# dwm1000arduino.net
KiCad netlist of a schematic drawn in Altium Designer
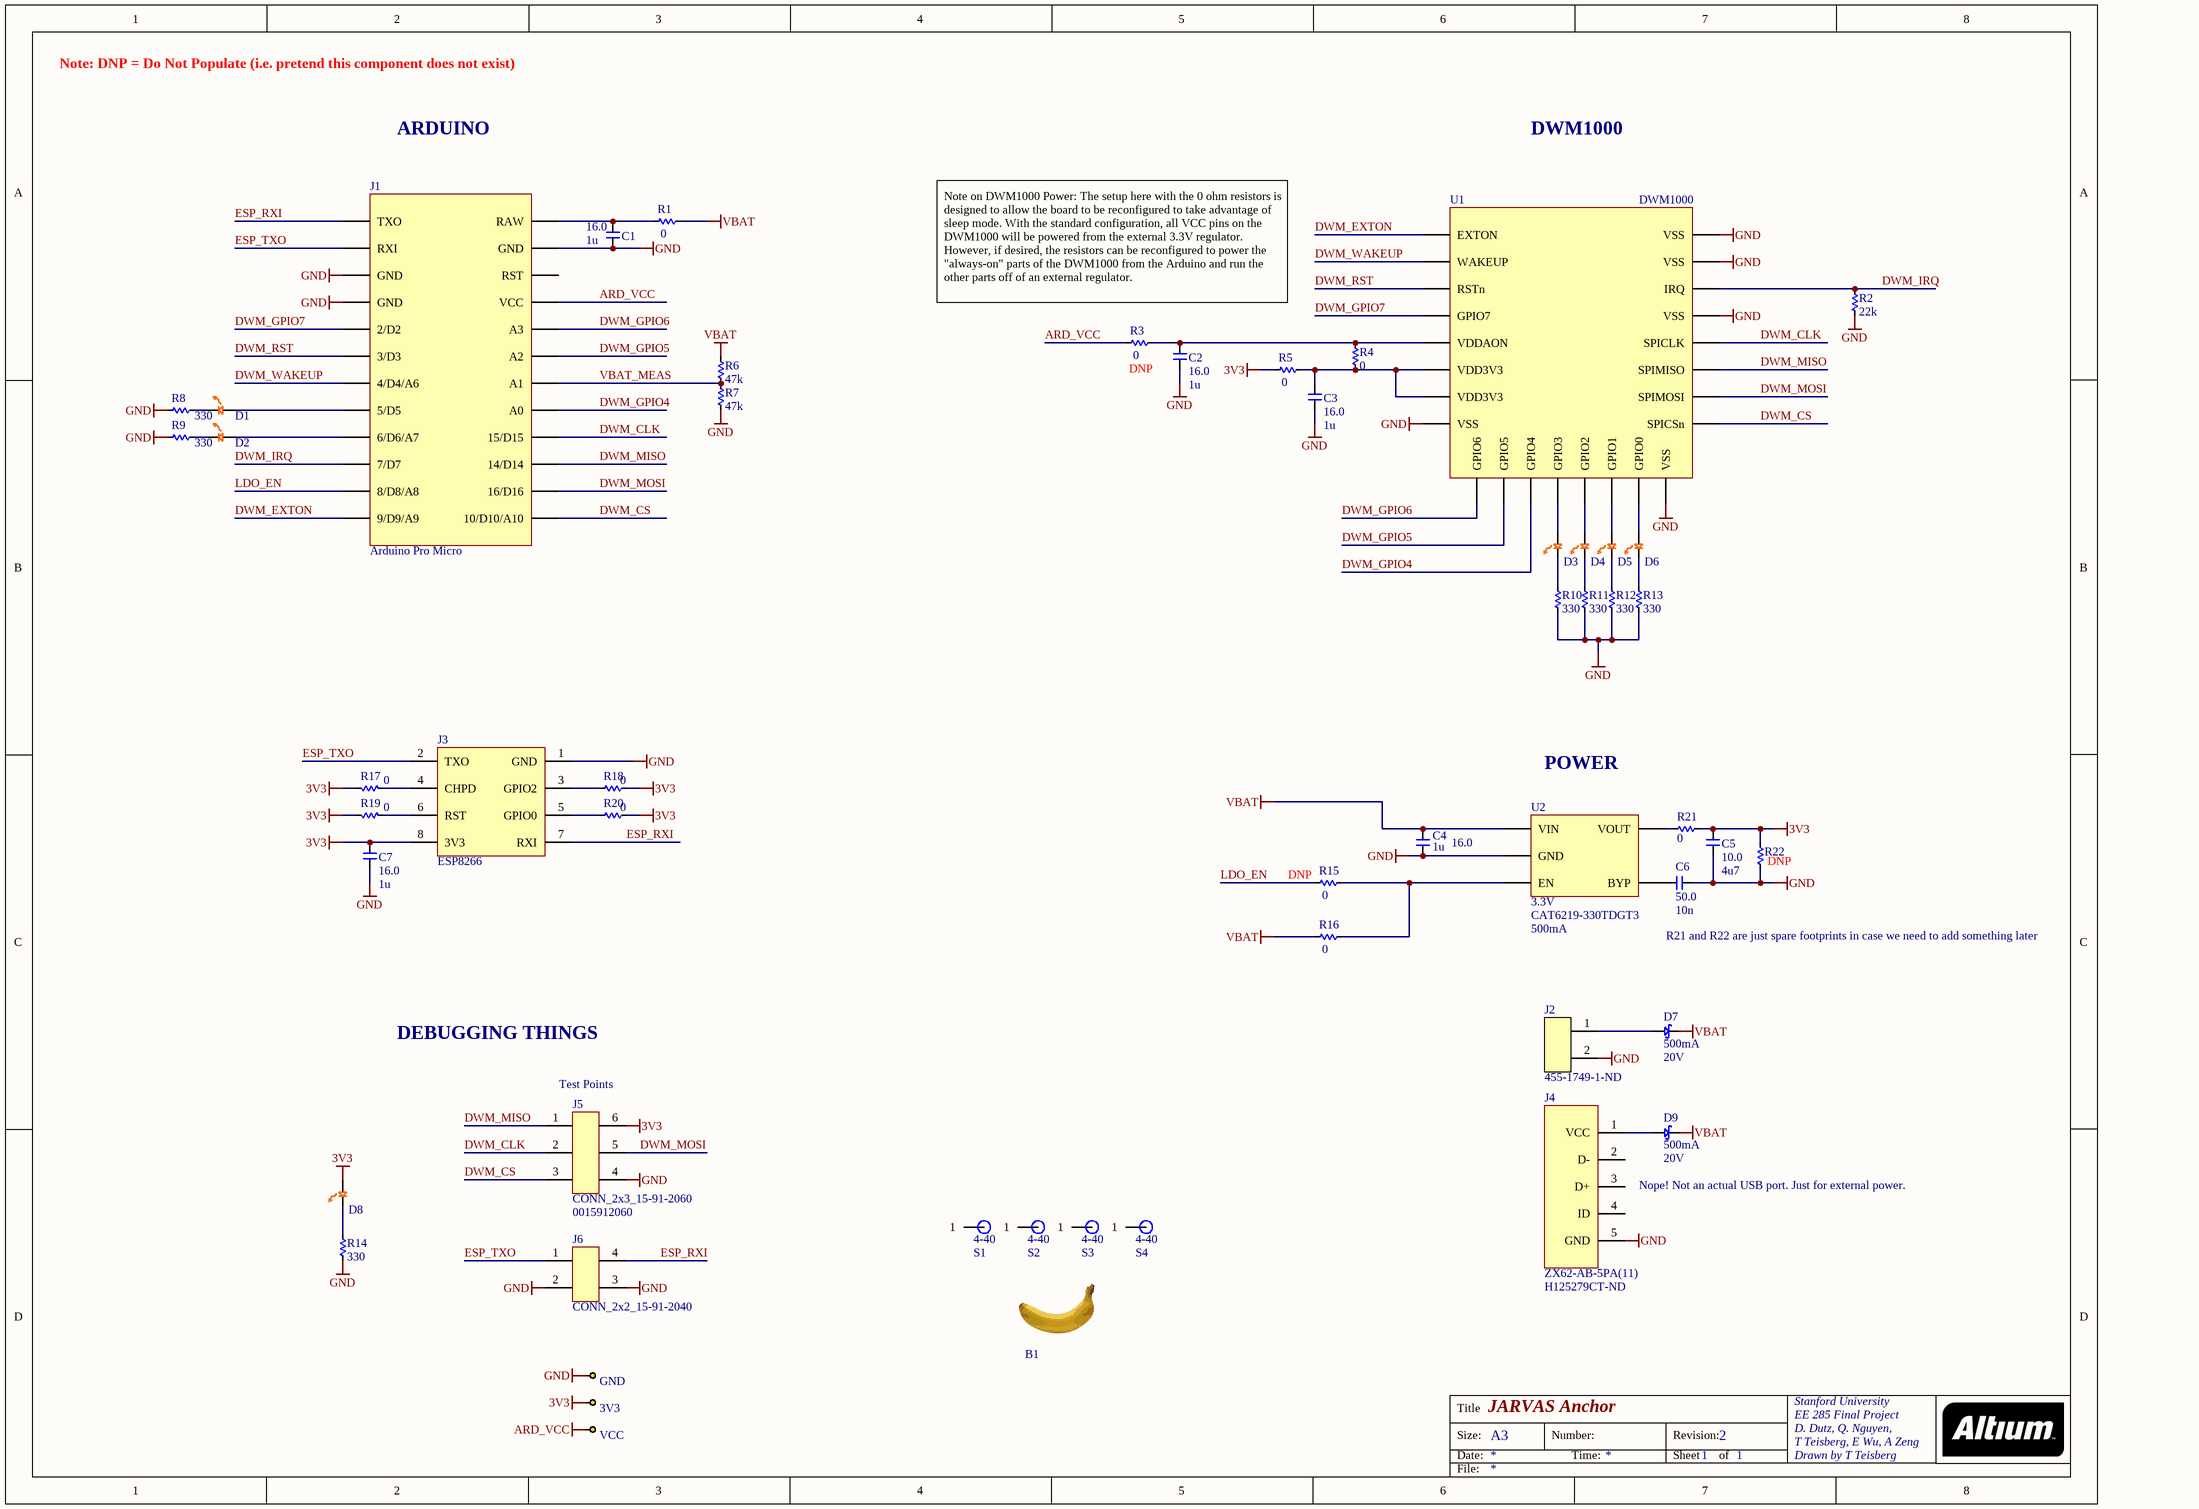
[diagram p0: dwm1000arduino.SchDoc]

(export (version "E")
  (design (tool "Eeschema 10.0.6"))
  (components
    (comp (ref "3V3")
      (value "TEST_KEYSTONE5015")
      (footprint "TP_KEYSTONE_5015")
      (description "PC TEST POINT MINIATURE SMT")
      (fields
        (field (name "MANUFACTURER") "Keystone Electronics")
        (field (name "MANUFACTURER PART NUMBER") "5015")
      )
      (libsource (lib "SSI") (part "TEST_KEYSTONE5015"))
    )
    (comp (ref "B1")
      (value "Banananannaa!")
      (footprint "BANANA_OPEN")
      (description "Banana for scale")
      (libsource (lib "SSI") (part "BANANA"))
    )
    (comp (ref "C1")
      (value "__template_cap")
      (footprint "C0603")
      (fields
        (field (name "VOLTAGE") "16.0")
        (field (name "HUMAN_VALUE") "1u")
        (field (name "TOLERANCE") "10%")
      )
      (libsource (lib "sscp") (part "__template_cap"))
    )
    (comp (ref "C2")
      (value "__template_cap")
      (footprint "C0603")
      (fields
        (field (name "VOLTAGE") "16.0")
        (field (name "HUMAN_VALUE") "1u")
        (field (name "TOLERANCE") "10%")
      )
      (libsource (lib "sscp") (part "__template_cap"))
    )
    (comp (ref "C3")
      (value "__template_cap")
      (footprint "C0603")
      (fields
        (field (name "VOLTAGE") "16.0")
        (field (name "HUMAN_VALUE") "1u")
        (field (name "TOLERANCE") "10%")
      )
      (libsource (lib "sscp") (part "__template_cap"))
    )
    (comp (ref "C4")
      (value "__template_cap")
      (footprint "C0603")
      (fields
        (field (name "VOLTAGE") "16.0")
        (field (name "HUMAN_VALUE") "1u")
        (field (name "TOLERANCE") "10%")
      )
      (libsource (lib "sscp") (part "__template_cap"))
    )
    (comp (ref "C5")
      (value "__template_cap")
      (footprint "C0603")
      (fields
        (field (name "VOLTAGE") "10.0")
        (field (name "HUMAN_VALUE") "4u7")
        (field (name "TOLERANCE") "10%")
      )
      (libsource (lib "sscp") (part "__template_cap"))
    )
    (comp (ref "C6")
      (value "__template_cap")
      (footprint "C0603")
      (fields
        (field (name "VOLTAGE") "50.0")
        (field (name "HUMAN_VALUE") "10n")
        (field (name "TOLERANCE") "5%")
      )
      (libsource (lib "sscp") (part "__template_cap"))
    )
    (comp (ref "C7")
      (value "__template_cap")
      (footprint "C0603")
      (fields
        (field (name "VOLTAGE") "16.0")
        (field (name "HUMAN_VALUE") "1u")
        (field (name "TOLERANCE") "10%")
      )
      (libsource (lib "sscp") (part "__template_cap"))
    )
    (comp (ref "D1")
      (value "LED")
      (footprint "LED0603")
      (description "Orange 605nm LED Indication - Discrete 2V 0603 (1608 Metric)")
      (fields
        (field (name "MANUFACTURER") "Lite-On Inc.")
        (field (name "MANUFACTURER PART NUMBER") "LTST-C190KFKT")
      )
      (libsource (lib "ee285") (part "LED_LTST-C190KFKT_ORANGE"))
    )
    (comp (ref "D2")
      (value "LED")
      (footprint "LED0603")
      (description "Orange 605nm LED Indication - Discrete 2V 0603 (1608 Metric)")
      (fields
        (field (name "MANUFACTURER") "Lite-On Inc.")
        (field (name "MANUFACTURER PART NUMBER") "LTST-C190KFKT")
      )
      (libsource (lib "ee285") (part "LED_LTST-C190KFKT_ORANGE"))
    )
    (comp (ref "D3")
      (value "LED")
      (footprint "LED0603")
      (description "Orange 605nm LED Indication - Discrete 2V 0603 (1608 Metric)")
      (fields
        (field (name "MANUFACTURER") "Lite-On Inc.")
        (field (name "MANUFACTURER PART NUMBER") "LTST-C190KFKT")
      )
      (libsource (lib "ee285") (part "LED_LTST-C190KFKT_ORANGE"))
    )
    (comp (ref "D4")
      (value "LED")
      (footprint "LED0603")
      (description "Orange 605nm LED Indication - Discrete 2V 0603 (1608 Metric)")
      (fields
        (field (name "MANUFACTURER") "Lite-On Inc.")
        (field (name "MANUFACTURER PART NUMBER") "LTST-C190KFKT")
      )
      (libsource (lib "ee285") (part "LED_LTST-C190KFKT_ORANGE"))
    )
    (comp (ref "D5")
      (value "LED")
      (footprint "LED0603")
      (description "Orange 605nm LED Indication - Discrete 2V 0603 (1608 Metric)")
      (fields
        (field (name "MANUFACTURER") "Lite-On Inc.")
        (field (name "MANUFACTURER PART NUMBER") "LTST-C190KFKT")
      )
      (libsource (lib "ee285") (part "LED_LTST-C190KFKT_ORANGE"))
    )
    (comp (ref "D6")
      (value "LED")
      (footprint "LED0603")
      (description "Orange 605nm LED Indication - Discrete 2V 0603 (1608 Metric)")
      (fields
        (field (name "MANUFACTURER") "Lite-On Inc.")
        (field (name "MANUFACTURER PART NUMBER") "LTST-C190KFKT")
      )
      (libsource (lib "ee285") (part "LED_LTST-C190KFKT_ORANGE"))
    )
    (comp (ref "D7")
      (value "SCHOTTKY_MBR0520L")
      (footprint "SOD123")
      (description "DIODE SCHOTTKY 0.5A 20V SOD-123")
      (fields
        (field (name "MANUFACTURER") "Fairchild Semiconductor")
        (field (name "MANUFACTURER PART NUMBER") "MBR0520L")
        (field (name "CURRENT - AVERAGE RECTIFIED (IO)") "500mA")
        (field (name "VOLTAGE - DC REVERSE (VR) (MAX)") "20V")
      )
      (libsource (lib "SSI") (part "SCHOTTKY_MBR0520L"))
    )
    (comp (ref "D8")
      (value "LED")
      (footprint "LED0603")
      (description "Orange 605nm LED Indication - Discrete 2V 0603 (1608 Metric)")
      (fields
        (field (name "MANUFACTURER") "Lite-On Inc.")
        (field (name "MANUFACTURER PART NUMBER") "LTST-C190KFKT")
      )
      (libsource (lib "ee285") (part "LED_LTST-C190KFKT_ORANGE"))
    )
    (comp (ref "D9")
      (value "SCHOTTKY_MBR0520L")
      (footprint "SOD123")
      (description "DIODE SCHOTTKY 0.5A 20V SOD-123")
      (fields
        (field (name "MANUFACTURER") "Fairchild Semiconductor")
        (field (name "MANUFACTURER PART NUMBER") "MBR0520L")
        (field (name "CURRENT - AVERAGE RECTIFIED (IO)") "500mA")
        (field (name "VOLTAGE - DC REVERSE (VR) (MAX)") "20V")
      )
      (libsource (lib "SSI") (part "SCHOTTKY_MBR0520L"))
    )
    (comp (ref "GND")
      (value "TEST_KEYSTONE5015")
      (footprint "TP_KEYSTONE_5015")
      (description "PC TEST POINT MINIATURE SMT")
      (fields
        (field (name "MANUFACTURER") "Keystone Electronics")
        (field (name "MANUFACTURER PART NUMBER") "5015")
      )
      (libsource (lib "SSI") (part "TEST_KEYSTONE5015"))
    )
    (comp (ref "J1")
      (value "Arduino Pro Micro")
      (footprint "ArduinoProMicro")
      (description "SFE Arduino Pro Micro 3.3 V / 8 MHz")
      (libsource (lib "ee285") (part "ArduinoProMicro_3V3_8MHz"))
    )
    (comp (ref "J2")
      (value "CONN JST 2POS SMD")
      (footprint "CONN_JST_PH_SM4_2PIN_RA")
      (description "CONN HEADER PH SIDE 2POS 2MM SMD")
      (fields
        (field (name "MANUFACTURER") "JST Sales America Inc.")
        (field (name "MANUFACTURER PART NUMBER") "S2B-PH-SM4-TB(LF)(SN)")
        (field (name "SUPPLIER PART NUMBER 1") "455-1749-1-ND")
      )
      (libsource (lib "SSI") (part "CONN_JST_2_PH"))
    )
    (comp (ref "J3")
      (value "ESP8266")
      (footprint "PCBComponent_1")
      (description "RF TXRX MODULE WIFI TRACE ANT")
      (fields
        (field (name "MANUFACTURER") "SparkFun Electronics")
        (field (name "MANUFACTURER PART NUMBER") "WRL-13678")
      )
      (libsource (lib "ee285") (part "ESP8266_Module"))
    )
    (comp (ref "J4")
      (value "CONN_USB_MICROAB_SMD_R/A")
      (footprint "HIROSE_ZX62-AB-5PA")
      (description "CONN RCPT MICRO USB AB SMD R/A")
      (fields
        (field (name "MANUFACTURER") "Hirose Electric Co Ltd")
        (field (name "MANUFACTURER PART NUMBER") "ZX62-AB-5PA(11)")
        (field (name "SUPPLIER PART NUMBER 1") "H125279CT-ND")
      )
      (libsource (lib "SSI") (part "CONN_USB_MICROAB_SMD_R/A"))
    )
    (comp (ref "J5")
      (value "CONN_2x3_15-91-2060")
      (footprint "MOLEX_15-91-2060")
      (description "CONN HEADER 6POS .100\" VERT TIN")
      (fields
        (field (name "MANUFACTURER") "Molex Inc")
        (field (name "MANUFACTURER PART NUMBER") "0015912060")
      )
      (libsource (lib "SSI") (part "CONN_2x3_15-91-2060"))
    )
    (comp (ref "J6")
      (value "CONN_2x2_15-91-2040")
      (footprint "MOLEX_15-91-2040")
      (description "CONN HEADER 4POS .100\" VERT TIN")
      (libsource (lib "SSI") (part "CONN_2x2_15-91-2040"))
    )
    (comp (ref "R1")
      (value "__template_resistor")
      (footprint "R0603")
      (description "RES SMD 0.0 OHM")
      (fields
        (field (name "MANUFACTURER PART NUMBER") "CRCW06030000Z0EA")
        (field (name "RESISTANCE (MACHINE READABLE)") "0")
        (field (name "MANUFACTURER") "Vishay Dale")
      )
      (libsource (lib "resistor") (part "__template_resistor"))
    )
    (comp (ref "R2")
      (value "22k")
      (footprint "R0603")
      (description "RES SMD 22K OHM 1% 1/10W 0603")
      (fields
        (field (name "MANUFACTURER PART NUMBER") "CRCW060322K0FKEA")
        (field (name "MANUFACTURER") "Vishay Dale")
      )
      (libsource (lib "resistor") (part "__template_resistor"))
    )
    (comp (ref "R3")
      (value "__template_resistor")
      (footprint "R0603")
      (description "RES SMD 0.0 OHM")
      (fields
        (field (name "MANUFACTURER PART NUMBER") "CRCW06030000Z0EA")
        (field (name "RESISTANCE (MACHINE READABLE)") "0")
        (field (name "MANUFACTURER") "Vishay Dale")
        (field (name "DNP") "DNP")
      )
      (libsource (lib "resistor") (part "__template_resistor"))
    )
    (comp (ref "R4")
      (value "__template_resistor")
      (footprint "R0603")
      (description "RES SMD 0.0 OHM")
      (fields
        (field (name "MANUFACTURER PART NUMBER") "CRCW06030000Z0EA")
        (field (name "RESISTANCE (MACHINE READABLE)") "0")
        (field (name "MANUFACTURER") "Vishay Dale")
      )
      (libsource (lib "resistor") (part "__template_resistor"))
    )
    (comp (ref "R5")
      (value "__template_resistor")
      (footprint "R0603")
      (description "RES SMD 0.0 OHM")
      (fields
        (field (name "MANUFACTURER PART NUMBER") "CRCW06030000Z0EA")
        (field (name "RESISTANCE (MACHINE READABLE)") "0")
        (field (name "MANUFACTURER") "Vishay Dale")
      )
      (libsource (lib "resistor") (part "__template_resistor"))
    )
    (comp (ref "R6")
      (value "47k")
      (footprint "R0603")
      (description "RES SMD 47K OHM 1% 1/10W 0603")
      (fields
        (field (name "MANUFACTURER PART NUMBER") "CRCW060347K0FKEA")
        (field (name "MANUFACTURER") "Vishay Dale")
      )
      (libsource (lib "resistor") (part "__template_resistor"))
    )
    (comp (ref "R7")
      (value "47k")
      (footprint "R0603")
      (description "RES SMD 47K OHM 1% 1/10W 0603")
      (fields
        (field (name "MANUFACTURER PART NUMBER") "CRCW060347K0FKEA")
        (field (name "MANUFACTURER") "Vishay Dale")
      )
      (libsource (lib "resistor") (part "__template_resistor"))
    )
    (comp (ref "R8")
      (value "330")
      (footprint "R0603")
      (description "RES SMD 330 OHM 1% 1/10W 0603")
      (fields
        (field (name "MANUFACTURER PART NUMBER") "CRCW0603330RFKEA")
        (field (name "MANUFACTURER") "Vishay Dale")
      )
      (libsource (lib "resistor") (part "__template_resistor"))
    )
    (comp (ref "R9")
      (value "330")
      (footprint "R0603")
      (description "RES SMD 330 OHM 1% 1/10W 0603")
      (fields
        (field (name "MANUFACTURER PART NUMBER") "CRCW0603330RFKEA")
        (field (name "MANUFACTURER") "Vishay Dale")
      )
      (libsource (lib "resistor") (part "__template_resistor"))
    )
    (comp (ref "R10")
      (value "330")
      (footprint "R0603")
      (description "RES SMD 330 OHM 1% 1/10W 0603")
      (fields
        (field (name "MANUFACTURER PART NUMBER") "CRCW0603330RFKEA")
        (field (name "MANUFACTURER") "Vishay Dale")
      )
      (libsource (lib "resistor") (part "__template_resistor"))
    )
    (comp (ref "R11")
      (value "330")
      (footprint "R0603")
      (description "RES SMD 330 OHM 1% 1/10W 0603")
      (fields
        (field (name "MANUFACTURER PART NUMBER") "CRCW0603330RFKEA")
        (field (name "MANUFACTURER") "Vishay Dale")
      )
      (libsource (lib "resistor") (part "__template_resistor"))
    )
    (comp (ref "R12")
      (value "330")
      (footprint "R0603")
      (description "RES SMD 330 OHM 1% 1/10W 0603")
      (fields
        (field (name "MANUFACTURER PART NUMBER") "CRCW0603330RFKEA")
        (field (name "MANUFACTURER") "Vishay Dale")
      )
      (libsource (lib "resistor") (part "__template_resistor"))
    )
    (comp (ref "R13")
      (value "330")
      (footprint "R0603")
      (description "RES SMD 330 OHM 1% 1/10W 0603")
      (fields
        (field (name "MANUFACTURER PART NUMBER") "CRCW0603330RFKEA")
        (field (name "MANUFACTURER") "Vishay Dale")
      )
      (libsource (lib "resistor") (part "__template_resistor"))
    )
    (comp (ref "R14")
      (value "330")
      (footprint "R0603")
      (description "RES SMD 330 OHM 1% 1/10W 0603")
      (fields
        (field (name "MANUFACTURER PART NUMBER") "CRCW0603330RFKEA")
        (field (name "MANUFACTURER") "Vishay Dale")
      )
      (libsource (lib "resistor") (part "__template_resistor"))
    )
    (comp (ref "R15")
      (value "__template_resistor")
      (footprint "R0603")
      (description "RES SMD 0.0 OHM")
      (fields
        (field (name "MANUFACTURER PART NUMBER") "CRCW06030000Z0EA")
        (field (name "RESISTANCE (MACHINE READABLE)") "0")
        (field (name "MANUFACTURER") "Vishay Dale")
        (field (name "DNP") "DNP")
      )
      (libsource (lib "resistor") (part "__template_resistor"))
    )
    (comp (ref "R16")
      (value "__template_resistor")
      (footprint "R0603")
      (description "RES SMD 0.0 OHM")
      (fields
        (field (name "MANUFACTURER PART NUMBER") "CRCW06030000Z0EA")
        (field (name "RESISTANCE (MACHINE READABLE)") "0")
        (field (name "MANUFACTURER") "Vishay Dale")
      )
      (libsource (lib "resistor") (part "__template_resistor"))
    )
    (comp (ref "R17")
      (value "__template_resistor")
      (footprint "R0603")
      (description "RES SMD 0.0 OHM")
      (fields
        (field (name "MANUFACTURER PART NUMBER") "CRCW06030000Z0EA")
        (field (name "RESISTANCE (MACHINE READABLE)") "0")
        (field (name "MANUFACTURER") "Vishay Dale")
      )
      (libsource (lib "resistor") (part "__template_resistor"))
    )
    (comp (ref "R18")
      (value "__template_resistor")
      (footprint "R0603")
      (description "RES SMD 0.0 OHM")
      (fields
        (field (name "MANUFACTURER PART NUMBER") "CRCW06030000Z0EA")
        (field (name "RESISTANCE (MACHINE READABLE)") "0")
        (field (name "MANUFACTURER") "Vishay Dale")
      )
      (libsource (lib "resistor") (part "__template_resistor"))
    )
    (comp (ref "R19")
      (value "__template_resistor")
      (footprint "R0603")
      (description "RES SMD 0.0 OHM")
      (fields
        (field (name "MANUFACTURER PART NUMBER") "CRCW06030000Z0EA")
        (field (name "RESISTANCE (MACHINE READABLE)") "0")
        (field (name "MANUFACTURER") "Vishay Dale")
      )
      (libsource (lib "resistor") (part "__template_resistor"))
    )
    (comp (ref "R20")
      (value "__template_resistor")
      (footprint "R0603")
      (description "RES SMD 0.0 OHM")
      (fields
        (field (name "MANUFACTURER PART NUMBER") "CRCW06030000Z0EA")
        (field (name "RESISTANCE (MACHINE READABLE)") "0")
        (field (name "MANUFACTURER") "Vishay Dale")
      )
      (libsource (lib "resistor") (part "__template_resistor"))
    )
    (comp (ref "R21")
      (value "0")
      (footprint "R0603")
      (description "RES SMD 0.0 OHM")
      (fields
        (field (name "MANUFACTURER PART NUMBER") "CRCW06030000Z0EA")
        (field (name "MANUFACTURER") "Vishay Dale")
      )
      (libsource (lib "resistor") (part "__template_resistor"))
    )
    (comp (ref "R22")
      (value "__template_resistor")
      (footprint "R0603")
      (description "RES SMD 0.0 OHM")
      (fields
        (field (name "MANUFACTURER PART NUMBER") "CRCW06030000Z0EA")
        (field (name "MANUFACTURER") "Vishay Dale")
        (field (name "DNP") "DNP")
      )
      (libsource (lib "resistor") (part "__template_resistor"))
    )
    (comp (ref "S1")
      (value "4-40 Machine screw")
      (footprint "SCREW_4-40")
      (libsource (lib "SSI") (part "SCREW_4-40"))
    )
    (comp (ref "S2")
      (value "4-40 Machine screw")
      (footprint "SCREW_4-40")
      (libsource (lib "SSI") (part "SCREW_4-40"))
    )
    (comp (ref "S3")
      (value "4-40 Machine screw")
      (footprint "SCREW_4-40")
      (libsource (lib "SSI") (part "SCREW_4-40"))
    )
    (comp (ref "S4")
      (value "4-40 Machine screw")
      (footprint "SCREW_4-40")
      (libsource (lib "SSI") (part "SCREW_4-40"))
    )
    (comp (ref "U1")
      (value "DWM1000")
      (footprint "DW1000")
      (fields (field (name "MANUFACTURER") "Decawave Limited"))
      (libsource (lib "ee285") (part "DWM1000"))
    )
    (comp (ref "U2")
      (value "3.3V LDO")
      (footprint "TSOT-23-5")
      (description "Linear Voltage Regulator IC Positive Fixed 1 Output 3.3V 500mA TSOT-23-5")
      (fields
        (field (name "MANUFACTURER") "ON Semiconductor")
        (field (name "VOLTAGE - OUTPUT") "3.3V")
        (field (name "MANUFACTURER PART NUMBER") "CAT6219-330TDGT3")
        (field (name "CURRENT - OUTPUT") "500mA")
      )
      (libsource (lib "ee285") (part "LDO_CAT6219_3V3"))
    )
    (comp (ref "VCC")
      (value "TEST_KEYSTONE5015")
      (footprint "TP_KEYSTONE_5015")
      (description "PC TEST POINT MINIATURE SMT")
      (fields
        (field (name "MANUFACTURER") "Keystone Electronics")
        (field (name "MANUFACTURER PART NUMBER") "5015")
      )
      (libsource (lib "SSI") (part "TEST_KEYSTONE5015"))
    )
  )
  (nets
    (net (code "1") (name "/DWM_CLK") (class "Default")
      (node (ref "J1") (pin "16") (pinfunction "15/D15_16") (pintype "passive"))
      (node (ref "J5") (pin "2") (pintype "passive"))
      (node (ref "U1") (pin "20") (pinfunction "SPICLK_20") (pintype "passive"))
    )
    (net (code "2") (name "/DWM_CS") (class "Default")
      (node (ref "J1") (pin "13") (pinfunction "10/D10/A10_13") (pintype "passive"))
      (node (ref "J5") (pin "3") (pintype "passive"))
      (node (ref "U1") (pin "17") (pinfunction "SPICSn_17") (pintype "passive"))
    )
    (net (code "3") (name "/DWM_EXTON") (class "Default")
      (node (ref "J1") (pin "12") (pinfunction "9/D9/A9_12") (pintype "passive"))
      (node (ref "U1") (pin "1") (pinfunction "EXTON_1") (pintype "passive"))
    )
    (net (code "4") (name "/DWM_GPIO4") (class "Default")
      (node (ref "J1") (pin "17") (pinfunction "A0_17") (pintype "passive"))
      (node (ref "U1") (pin "11") (pinfunction "GPIO4_11") (pintype "passive"))
    )
    (net (code "5") (name "/DWM_GPIO5") (class "Default")
      (node (ref "J1") (pin "19") (pinfunction "A2_19") (pintype "passive"))
      (node (ref "U1") (pin "10") (pinfunction "GPIO5_10") (pintype "passive"))
    )
    (net (code "6") (name "/DWM_GPIO6") (class "Default")
      (node (ref "J1") (pin "20") (pinfunction "A3_20") (pintype "passive"))
      (node (ref "U1") (pin "9") (pinfunction "GPIO6_9") (pintype "passive"))
    )
    (net (code "7") (name "/DWM_GPIO7") (class "Default")
      (node (ref "J1") (pin "5") (pinfunction "2/D2_5") (pintype "passive"))
      (node (ref "U1") (pin "4") (pinfunction "GPIO7_4") (pintype "passive"))
    )
    (net (code "8") (name "/DWM_IRQ") (class "Default")
      (node (ref "J1") (pin "10") (pinfunction "7/D7_10") (pintype "passive"))
      (node (ref "R2") (pin "2") (pintype "passive"))
      (node (ref "U1") (pin "22") (pinfunction "IRQ_22") (pintype "passive"))
    )
    (net (code "9") (name "/DWM_MISO") (class "Default")
      (node (ref "J1") (pin "15") (pinfunction "14/D14_15") (pintype "passive"))
      (node (ref "J5") (pin "1") (pintype "passive"))
      (node (ref "U1") (pin "19") (pinfunction "SPIMISO_19") (pintype "passive"))
    )
    (net (code "10") (name "/DWM_MOSI") (class "Default")
      (node (ref "J1") (pin "14") (pinfunction "16/D16_14") (pintype "passive"))
      (node (ref "J5") (pin "5") (pintype "passive"))
      (node (ref "U1") (pin "18") (pinfunction "SPIMOSI_18") (pintype "passive"))
    )
    (net (code "11") (name "/DWM_RST") (class "Default")
      (node (ref "J1") (pin "6") (pinfunction "3/D3_6") (pintype "passive"))
      (node (ref "U1") (pin "3") (pinfunction "RSTn_3") (pintype "passive"))
    )
    (net (code "12") (name "/DWM_WAKEUP") (class "Default")
      (node (ref "J1") (pin "7") (pinfunction "4/D4/A6_7") (pintype "passive"))
      (node (ref "U1") (pin "2") (pinfunction "WAKEUP_2") (pintype "passive"))
    )
    (net (code "13") (name "/ESP_RXI") (class "Default")
      (node (ref "J1") (pin "1") (pinfunction "TXO_1") (pintype "passive"))
      (node (ref "J3") (pin "7") (pinfunction "RXI_7") (pintype "passive"))
      (node (ref "J6") (pin "4") (pintype "passive"))
    )
    (net (code "14") (name "/ESP_TXO") (class "Default")
      (node (ref "J1") (pin "2") (pinfunction "RXI_2") (pintype "passive"))
      (node (ref "J3") (pin "2") (pinfunction "TXO_2") (pintype "passive"))
      (node (ref "J6") (pin "1") (pintype "passive"))
    )
    (net (code "15") (name "/LDO_EN") (class "Default")
      (node (ref "J1") (pin "11") (pinfunction "8/D8/A8_11") (pintype "passive"))
      (node (ref "R15") (pin "1") (pintype "passive"))
    )
    (net (code "16") (name "/VBAT_MEAS") (class "Default")
      (node (ref "J1") (pin "18") (pinfunction "A1_18") (pintype "passive"))
      (node (ref "R6") (pin "1") (pintype "passive"))
      (node (ref "R7") (pin "2") (pintype "passive"))
    )
    (net (code "17") (name "3V3") (class "Default")
      (node (ref "3V3") (pin "1") (pintype "passive"))
      (node (ref "C5") (pin "2") (pintype "passive"))
      (node (ref "C7") (pin "1") (pintype "passive"))
      (node (ref "D8") (pin "A") (pintype "passive"))
      (node (ref "J3") (pin "8") (pinfunction "3V3_8") (pintype "passive"))
      (node (ref "J5") (pin "6") (pintype "passive"))
      (node (ref "R17") (pin "2") (pintype "passive"))
      (node (ref "R18") (pin "2") (pintype "passive"))
      (node (ref "R19") (pin "2") (pintype "passive"))
      (node (ref "R20") (pin "2") (pintype "passive"))
      (node (ref "R21") (pin "2") (pintype "passive"))
      (node (ref "R22") (pin "2") (pintype "passive"))
      (node (ref "R5") (pin "1") (pintype "passive"))
    )
    (net (code "18") (name "ARD_VCC") (class "Default")
      (node (ref "J1") (pin "21") (pinfunction "VCC_21") (pintype "passive"))
      (node (ref "R3") (pin "1") (pintype "passive"))
      (node (ref "VCC") (pin "1") (pintype "passive"))
    )
    (net (code "19") (name "GND") (class "Default")
      (node (ref "C1") (pin "2") (pintype "passive"))
      (node (ref "C2") (pin "2") (pintype "passive"))
      (node (ref "C3") (pin "2") (pintype "passive"))
      (node (ref "C4") (pin "1") (pintype "passive"))
      (node (ref "C5") (pin "1") (pintype "passive"))
      (node (ref "C6") (pin "2") (pintype "passive"))
      (node (ref "C7") (pin "2") (pintype "passive"))
      (node (ref "GND") (pin "1") (pintype "passive"))
      (node (ref "J1") (pin "23") (pinfunction "GND_23") (pintype "passive"))
      (node (ref "J1") (pin "3") (pinfunction "GND_3") (pintype "passive"))
      (node (ref "J1") (pin "4") (pinfunction "GND_4") (pintype "passive"))
      (node (ref "J2") (pin "2") (pinfunction "2_2") (pintype "passive"))
      (node (ref "J3") (pin "1") (pinfunction "GND_1") (pintype "passive"))
      (node (ref "J4") (pin "5") (pinfunction "GND_5") (pintype "passive"))
      (node (ref "J5") (pin "4") (pintype "passive"))
      (node (ref "J6") (pin "2") (pintype "passive"))
      (node (ref "J6") (pin "3") (pintype "passive"))
      (node (ref "R10") (pin "1") (pintype "passive"))
      (node (ref "R11") (pin "1") (pintype "passive"))
      (node (ref "R12") (pin "1") (pintype "passive"))
      (node (ref "R13") (pin "1") (pintype "passive"))
      (node (ref "R14") (pin "1") (pintype "passive"))
      (node (ref "R2") (pin "1") (pintype "passive"))
      (node (ref "R22") (pin "1") (pintype "passive"))
      (node (ref "R7") (pin "1") (pintype "passive"))
      (node (ref "R8") (pin "2") (pintype "passive"))
      (node (ref "R9") (pin "2") (pintype "passive"))
      (node (ref "U1") (pin "16") (pinfunction "VSS_16") (pintype "passive"))
      (node (ref "U1") (pin "21") (pinfunction "VSS_21") (pintype "passive"))
      (node (ref "U1") (pin "23") (pinfunction "VSS_23") (pintype "passive"))
      (node (ref "U1") (pin "24") (pinfunction "VSS_24") (pintype "passive"))
      (node (ref "U1") (pin "8") (pinfunction "VSS_8") (pintype "passive"))
      (node (ref "U2") (pin "2") (pinfunction "GND_2") (pintype "passive"))
    )
    (net (code "20") (name "Net-(C3-Pad1)") (class "Default")
      (node (ref "C3") (pin "1") (pintype "passive"))
      (node (ref "R4") (pin "1") (pintype "passive"))
      (node (ref "R5") (pin "2") (pintype "passive"))
      (node (ref "U1") (pin "6") (pinfunction "VDD3V3_6") (pintype "passive"))
      (node (ref "U1") (pin "7") (pinfunction "VDD3V3_7") (pintype "passive"))
    )
    (net (code "21") (name "Net-(D1-PadK)") (class "Default")
      (node (ref "D1") (pin "K") (pintype "passive"))
      (node (ref "R8") (pin "1") (pintype "passive"))
    )
    (net (code "22") (name "Net-(D2-PadK)") (class "Default")
      (node (ref "D2") (pin "K") (pintype "passive"))
      (node (ref "R9") (pin "1") (pintype "passive"))
    )
    (net (code "23") (name "Net-(D3-PadK)") (class "Default")
      (node (ref "D3") (pin "K") (pintype "passive"))
      (node (ref "R10") (pin "2") (pintype "passive"))
    )
    (net (code "24") (name "Net-(D4-PadK)") (class "Default")
      (node (ref "D4") (pin "K") (pintype "passive"))
      (node (ref "R11") (pin "2") (pintype "passive"))
    )
    (net (code "25") (name "Net-(D5-PadK)") (class "Default")
      (node (ref "D5") (pin "K") (pintype "passive"))
      (node (ref "R12") (pin "2") (pintype "passive"))
    )
    (net (code "26") (name "Net-(D6-PadK)") (class "Default")
      (node (ref "D6") (pin "K") (pintype "passive"))
      (node (ref "R13") (pin "2") (pintype "passive"))
    )
    (net (code "27") (name "Net-(D7-Pad1)") (class "Default")
      (node (ref "D7") (pin "1") (pintype "passive"))
      (node (ref "J2") (pin "1") (pinfunction "1_1") (pintype "passive"))
    )
    (net (code "28") (name "Net-(D8-PadK)") (class "Default")
      (node (ref "D8") (pin "K") (pintype "passive"))
      (node (ref "R14") (pin "2") (pintype "passive"))
    )
    (net (code "29") (name "Net-(J1-5{slash}D5)") (class "Default")
      (node (ref "D1") (pin "A") (pintype "passive"))
      (node (ref "J1") (pin "8") (pinfunction "5/D5_8") (pintype "passive"))
    )
    (net (code "30") (name "Net-(J1-6{slash}D6{slash}A7)") (class "Default")
      (node (ref "D2") (pin "A") (pintype "passive"))
      (node (ref "J1") (pin "9") (pinfunction "6/D6/A7_9") (pintype "passive"))
    )
    (net (code "31") (name "Net-(J1-RAW)") (class "Default")
      (node (ref "C1") (pin "1") (pintype "passive"))
      (node (ref "J1") (pin "24") (pinfunction "RAW_24") (pintype "passive"))
      (node (ref "R1") (pin "1") (pintype "passive"))
    )
    (net (code "32") (name "Net-(J3-CHPD)") (class "Default")
      (node (ref "J3") (pin "4") (pinfunction "CHPD_4") (pintype "passive"))
      (node (ref "R17") (pin "1") (pintype "passive"))
    )
    (net (code "33") (name "Net-(J3-GPIO0)") (class "Default")
      (node (ref "J3") (pin "5") (pinfunction "GPIO0_5") (pintype "passive"))
      (node (ref "R20") (pin "1") (pintype "passive"))
    )
    (net (code "34") (name "Net-(J3-GPIO2)") (class "Default")
      (node (ref "J3") (pin "3") (pinfunction "GPIO2_3") (pintype "passive"))
      (node (ref "R18") (pin "1") (pintype "passive"))
    )
    (net (code "35") (name "Net-(J3-RST)") (class "Default")
      (node (ref "J3") (pin "6") (pinfunction "RST_6") (pintype "passive"))
      (node (ref "R19") (pin "1") (pintype "passive"))
    )
    (net (code "36") (name "Net-(J4-VCC)") (class "Default")
      (node (ref "D9") (pin "1") (pintype "passive"))
      (node (ref "J4") (pin "1") (pinfunction "VCC_1") (pintype "passive"))
    )
    (net (code "37") (name "Net-(U1-GPIO0)") (class "Default")
      (node (ref "D6") (pin "A") (pintype "passive"))
      (node (ref "U1") (pin "15") (pinfunction "GPIO0_15") (pintype "passive"))
    )
    (net (code "38") (name "Net-(U1-GPIO1)") (class "Default")
      (node (ref "D5") (pin "A") (pintype "passive"))
      (node (ref "U1") (pin "14") (pinfunction "GPIO1_14") (pintype "passive"))
    )
    (net (code "39") (name "Net-(U1-GPIO2)") (class "Default")
      (node (ref "D4") (pin "A") (pintype "passive"))
      (node (ref "U1") (pin "13") (pinfunction "GPIO2_13") (pintype "passive"))
    )
    (net (code "40") (name "Net-(U1-GPIO3)") (class "Default")
      (node (ref "D3") (pin "A") (pintype "passive"))
      (node (ref "U1") (pin "12") (pinfunction "GPIO3_12") (pintype "passive"))
    )
    (net (code "41") (name "Net-(U1-VDDAON)") (class "Default")
      (node (ref "C2") (pin "1") (pintype "passive"))
      (node (ref "R3") (pin "2") (pintype "passive"))
      (node (ref "R4") (pin "2") (pintype "passive"))
      (node (ref "U1") (pin "5") (pinfunction "VDDAON_5") (pintype "passive"))
    )
    (net (code "42") (name "Net-(U2-BYP)") (class "Default")
      (node (ref "C6") (pin "1") (pintype "passive"))
      (node (ref "U2") (pin "4") (pinfunction "BYP_4") (pintype "passive"))
    )
    (net (code "43") (name "Net-(U2-EN)") (class "Default")
      (node (ref "R15") (pin "2") (pintype "passive"))
      (node (ref "R16") (pin "2") (pintype "passive"))
      (node (ref "U2") (pin "3") (pinfunction "EN_3") (pintype "passive"))
    )
    (net (code "44") (name "Net-(U2-VOUT)") (class "Default")
      (node (ref "R21") (pin "1") (pintype "passive"))
      (node (ref "U2") (pin "5") (pinfunction "VOUT_5") (pintype "passive"))
    )
    (net (code "45") (name "VBAT") (class "Default")
      (node (ref "C4") (pin "2") (pintype "passive"))
      (node (ref "D7") (pin "2") (pintype "passive"))
      (node (ref "D9") (pin "2") (pintype "passive"))
      (node (ref "R1") (pin "2") (pintype "passive"))
      (node (ref "R16") (pin "1") (pintype "passive"))
      (node (ref "R6") (pin "2") (pintype "passive"))
      (node (ref "U2") (pin "1") (pinfunction "VIN_1") (pintype "passive"))
    )
    (net (code "46") (name "unconnected-(J1-RST-Pad22)") (class "Default")
      (node (ref "J1") (pin "22") (pinfunction "RST_22") (pintype "passive"))
    )
    (net (code "47") (name "unconnected-(J4-D+-Pad3)") (class "Default")
      (node (ref "J4") (pin "3") (pinfunction "D+_3") (pintype "passive"))
    )
    (net (code "48") (name "unconnected-(J4-D--Pad2)") (class "Default")
      (node (ref "J4") (pin "2") (pinfunction "D-_2") (pintype "passive"))
    )
    (net (code "49") (name "unconnected-(J4-ID-Pad4)") (class "Default")
      (node (ref "J4") (pin "4") (pinfunction "ID_4") (pintype "passive"))
    )
    (net (code "50") (name "unconnected-(S1-Pad1)") (class "Default")
      (node (ref "S1") (pin "1") (pinfunction "1_1") (pintype "passive"))
    )
    (net (code "51") (name "unconnected-(S2-Pad1)") (class "Default")
      (node (ref "S2") (pin "1") (pinfunction "1_1") (pintype "passive"))
    )
    (net (code "52") (name "unconnected-(S3-Pad1)") (class "Default")
      (node (ref "S3") (pin "1") (pinfunction "1_1") (pintype "passive"))
    )
    (net (code "53") (name "unconnected-(S4-Pad1)") (class "Default")
      (node (ref "S4") (pin "1") (pinfunction "1_1") (pintype "passive"))
    )
  )
)
